# lights_a.net
KiCad netlist of a schematic drawn in EAGLE
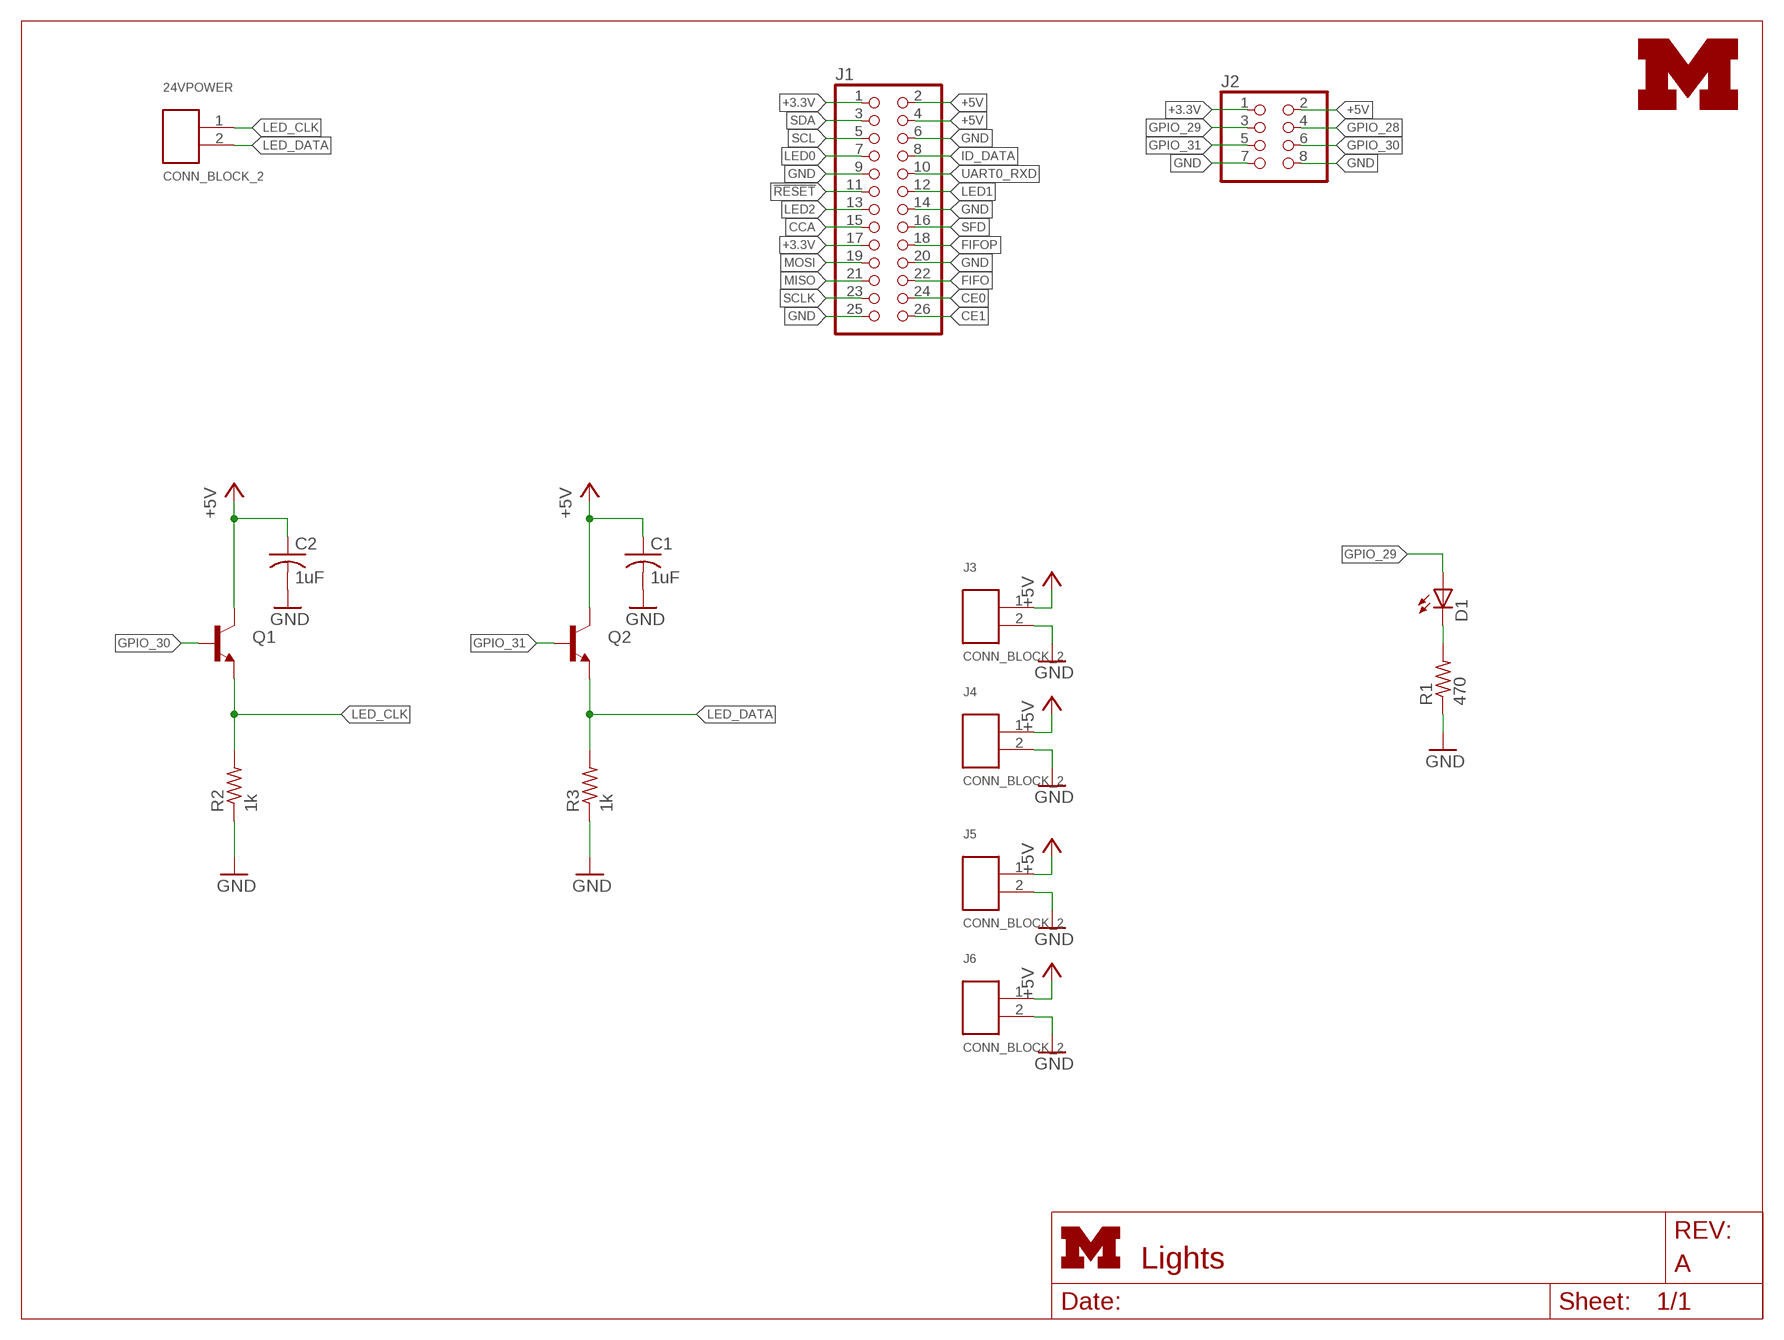
[diagram p0: schematic, sheet 1]

(export (version "E")
  (design (tool "Eeschema 10.0.6"))
  (components
    (comp (ref "24VPOWER")
      (value "CONN_BLOCK_2")
      (footprint "eagle-import:CONN_BLOCK_2")
      (libsource (lib "eagle-import") (part "CONN_BLOCK_2"))
    )
    (comp (ref "C1")
      (value "1uF")
      (footprint "eagle-import:C0603")
      (libsource (lib "eagle-import") (part "C-USC0603"))
    )
    (comp (ref "C2")
      (value "1uF")
      (footprint "eagle-import:C0603")
      (libsource (lib "eagle-import") (part "C-USC0603"))
    )
    (comp (ref "D1")
      (value "LED0603")
      (footprint "eagle-import:LED-0603")
      (libsource (lib "eagle-import") (part "LED0603"))
    )
    (comp (ref "J1")
      (value "PINHD-2X13")
      (footprint "eagle-import:2X13")
      (libsource (lib "eagle-import") (part "PINHD-2X13"))
    )
    (comp (ref "J2")
      (value "PINHD-2X4")
      (footprint "eagle-import:2X04")
      (libsource (lib "eagle-import") (part "PINHD-2X4"))
    )
    (comp (ref "J3")
      (value "CONN_BLOCK_2")
      (footprint "eagle-import:CONN_BLOCK_2")
      (libsource (lib "eagle-import") (part "CONN_BLOCK_2"))
    )
    (comp (ref "J4")
      (value "CONN_BLOCK_2")
      (footprint "eagle-import:CONN_BLOCK_2")
      (libsource (lib "eagle-import") (part "CONN_BLOCK_2"))
    )
    (comp (ref "J5")
      (value "CONN_BLOCK_2")
      (footprint "eagle-import:CONN_BLOCK_2")
      (libsource (lib "eagle-import") (part "CONN_BLOCK_2"))
    )
    (comp (ref "J6")
      (value "CONN_BLOCK_2")
      (footprint "eagle-import:CONN_BLOCK_2")
      (libsource (lib "eagle-import") (part "CONN_BLOCK_2"))
    )
    (comp (ref "Q1")
      (value "TRANSISTOR_NPNSOT23")
      (footprint "eagle-import:SOT23")
      (libsource (lib "eagle-import") (part "TRANSISTOR_NPNSOT23"))
    )
    (comp (ref "Q2")
      (value "TRANSISTOR_NPNSOT23")
      (footprint "eagle-import:SOT23")
      (libsource (lib "eagle-import") (part "TRANSISTOR_NPNSOT23"))
    )
    (comp (ref "R1")
      (value "470")
      (footprint "eagle-import:R0603")
      (libsource (lib "eagle-import") (part "R-US_R0603"))
    )
    (comp (ref "R2")
      (value "1k")
      (footprint "eagle-import:R0603")
      (libsource (lib "eagle-import") (part "R-US_R0603"))
    )
    (comp (ref "R3")
      (value "1k")
      (footprint "eagle-import:R0603")
      (libsource (lib "eagle-import") (part "R-US_R0603"))
    )
    (comp (ref "U$1")
      (value "UMICH_SOLID_SMALL")
      (footprint "eagle-import:UMICH_SOLID_75MIL")
      (libsource (lib "eagle-import") (part "UMICH_SOLID_SMALL"))
    )
  )
  (nets
    (net (code "1") (name "+3.3V") (class "Default")
      (node (ref "J1") (pin "1") (pinfunction "1_1") (pintype "passive"))
      (node (ref "J1") (pin "17") (pinfunction "17_17") (pintype "passive"))
      (node (ref "J2") (pin "1") (pinfunction "1_1") (pintype "passive"))
    )
    (net (code "2") (name "+5V") (class "Default")
      (node (ref "C1") (pin "1") (pinfunction "1_1") (pintype "passive"))
      (node (ref "C2") (pin "1") (pinfunction "1_1") (pintype "passive"))
      (node (ref "J1") (pin "2") (pinfunction "2_2") (pintype "passive"))
      (node (ref "J1") (pin "4") (pinfunction "4_4") (pintype "passive"))
      (node (ref "J2") (pin "2") (pinfunction "2_2") (pintype "passive"))
      (node (ref "J3") (pin "1") (pinfunction "1_1") (pintype "bidirectional"))
      (node (ref "J4") (pin "1") (pinfunction "1_1") (pintype "bidirectional"))
      (node (ref "J5") (pin "1") (pinfunction "1_1") (pintype "bidirectional"))
      (node (ref "J6") (pin "1") (pinfunction "1_1") (pintype "bidirectional"))
      (node (ref "Q1") (pin "3") (pinfunction "C_3") (pintype "passive"))
      (node (ref "Q2") (pin "3") (pinfunction "C_3") (pintype "passive"))
    )
    (net (code "3") (name "/~{RESET}") (class "Default")
      (node (ref "J1") (pin "11") (pinfunction "11_11") (pintype "passive"))
    )
    (net (code "4") (name "CCA") (class "Default")
      (node (ref "J1") (pin "15") (pinfunction "15_15") (pintype "passive"))
    )
    (net (code "5") (name "CE0") (class "Default")
      (node (ref "J1") (pin "24") (pinfunction "24_24") (pintype "passive"))
    )
    (net (code "6") (name "CE1") (class "Default")
      (node (ref "J1") (pin "26") (pinfunction "26_26") (pintype "passive"))
    )
    (net (code "7") (name "FIFO") (class "Default")
      (node (ref "J1") (pin "22") (pinfunction "22_22") (pintype "passive"))
    )
    (net (code "8") (name "FIFOP") (class "Default")
      (node (ref "J1") (pin "18") (pinfunction "18_18") (pintype "passive"))
    )
    (net (code "9") (name "GND") (class "Default")
      (node (ref "C1") (pin "2") (pinfunction "2_2") (pintype "passive"))
      (node (ref "C2") (pin "2") (pinfunction "2_2") (pintype "passive"))
      (node (ref "J1") (pin "14") (pinfunction "14_14") (pintype "passive"))
      (node (ref "J1") (pin "20") (pinfunction "20_20") (pintype "passive"))
      (node (ref "J1") (pin "25") (pinfunction "25_25") (pintype "passive"))
      (node (ref "J1") (pin "6") (pinfunction "6_6") (pintype "passive"))
      (node (ref "J1") (pin "9") (pinfunction "9_9") (pintype "passive"))
      (node (ref "J2") (pin "7") (pinfunction "7_7") (pintype "passive"))
      (node (ref "J2") (pin "8") (pinfunction "8_8") (pintype "passive"))
      (node (ref "J3") (pin "2") (pinfunction "2_2") (pintype "bidirectional"))
      (node (ref "J4") (pin "2") (pinfunction "2_2") (pintype "bidirectional"))
      (node (ref "J5") (pin "2") (pinfunction "2_2") (pintype "bidirectional"))
      (node (ref "J6") (pin "2") (pinfunction "2_2") (pintype "bidirectional"))
      (node (ref "R1") (pin "1") (pinfunction "1_1") (pintype "passive"))
      (node (ref "R2") (pin "1") (pinfunction "1_1") (pintype "passive"))
      (node (ref "R3") (pin "1") (pinfunction "1_1") (pintype "passive"))
    )
    (net (code "10") (name "GPIO_28") (class "Default")
      (node (ref "J2") (pin "4") (pinfunction "4_4") (pintype "passive"))
    )
    (net (code "11") (name "GPIO_29") (class "Default")
      (node (ref "D1") (pin "A") (pinfunction "A_A") (pintype "passive"))
      (node (ref "J2") (pin "3") (pinfunction "3_3") (pintype "passive"))
    )
    (net (code "12") (name "GPIO_30") (class "Default")
      (node (ref "J2") (pin "6") (pinfunction "6_6") (pintype "passive"))
      (node (ref "Q1") (pin "1") (pinfunction "B_1") (pintype "passive"))
    )
    (net (code "13") (name "GPIO_31") (class "Default")
      (node (ref "J2") (pin "5") (pinfunction "5_5") (pintype "passive"))
      (node (ref "Q2") (pin "1") (pinfunction "B_1") (pintype "passive"))
    )
    (net (code "14") (name "ID_DATA") (class "Default")
      (node (ref "J1") (pin "8") (pinfunction "8_8") (pintype "passive"))
    )
    (net (code "15") (name "LED0") (class "Default")
      (node (ref "J1") (pin "7") (pinfunction "7_7") (pintype "passive"))
    )
    (net (code "16") (name "LED1") (class "Default")
      (node (ref "J1") (pin "12") (pinfunction "12_12") (pintype "passive"))
    )
    (net (code "17") (name "LED2") (class "Default")
      (node (ref "J1") (pin "13") (pinfunction "13_13") (pintype "passive"))
    )
    (net (code "18") (name "LED_CLK") (class "Default")
      (node (ref "24VPOWER") (pin "1") (pinfunction "1_1") (pintype "bidirectional"))
      (node (ref "Q1") (pin "2") (pinfunction "E_2") (pintype "passive"))
      (node (ref "R2") (pin "2") (pinfunction "2_2") (pintype "passive"))
    )
    (net (code "19") (name "LED_DATA") (class "Default")
      (node (ref "24VPOWER") (pin "2") (pinfunction "2_2") (pintype "bidirectional"))
      (node (ref "Q2") (pin "2") (pinfunction "E_2") (pintype "passive"))
      (node (ref "R3") (pin "2") (pinfunction "2_2") (pintype "passive"))
    )
    (net (code "20") (name "MISO") (class "Default")
      (node (ref "J1") (pin "21") (pinfunction "21_21") (pintype "passive"))
    )
    (net (code "21") (name "MOSI") (class "Default")
      (node (ref "J1") (pin "19") (pinfunction "19_19") (pintype "passive"))
    )
    (net (code "22") (name "Net-(D1-PadC)") (class "Default")
      (node (ref "D1") (pin "C") (pinfunction "C_C") (pintype "passive"))
      (node (ref "R1") (pin "2") (pinfunction "2_2") (pintype "passive"))
    )
    (net (code "23") (name "SCL") (class "Default")
      (node (ref "J1") (pin "5") (pinfunction "5_5") (pintype "passive"))
    )
    (net (code "24") (name "SCLK") (class "Default")
      (node (ref "J1") (pin "23") (pinfunction "23_23") (pintype "passive"))
    )
    (net (code "25") (name "SDA") (class "Default")
      (node (ref "J1") (pin "3") (pinfunction "3_3") (pintype "passive"))
    )
    (net (code "26") (name "SFD") (class "Default")
      (node (ref "J1") (pin "16") (pinfunction "16_16") (pintype "passive"))
    )
    (net (code "27") (name "UART0_RXD") (class "Default")
      (node (ref "J1") (pin "10") (pinfunction "10_10") (pintype "passive"))
    )
  )
)
